# THAT4305_Comp_CE.net
KiCad netlist of a schematic drawn in EAGLE
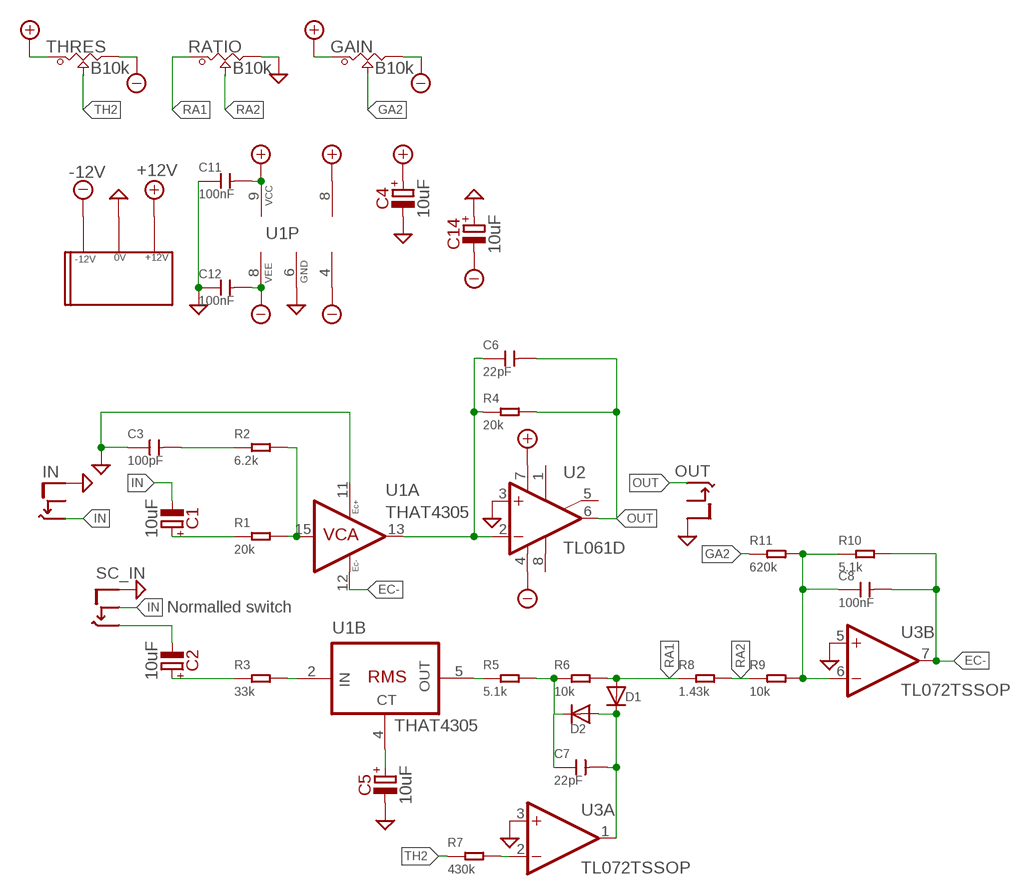
[diagram p0: schematic, sheet 1]

(export (version "E")
  (design (tool "Eeschema 10.0.6"))
  (components
    (comp (ref "C1")
      (value "10uF")
      (footprint "eagle-import:PAN_B")
      (libsource (lib "eagle-import") (part "PAN_B"))
    )
    (comp (ref "C2")
      (value "10uF")
      (footprint "eagle-import:PAN_B")
      (libsource (lib "eagle-import") (part "PAN_B"))
    )
    (comp (ref "C3")
      (value "100pF")
      (footprint "eagle-import:C0805")
      (fields (field (name "MPN") "CC0805KKX7R8BB105"))
      (libsource (lib "eagle-import") (part "CERAMIC-1UF-25V-10%-X7R(0805)"))
    )
    (comp (ref "C4")
      (value "10uF")
      (footprint "eagle-import:PAN_B")
      (libsource (lib "eagle-import") (part "PAN_B"))
    )
    (comp (ref "C5")
      (value "10uF")
      (footprint "eagle-import:PAN_B")
      (libsource (lib "eagle-import") (part "PAN_B"))
    )
    (comp (ref "C6")
      (value "22pF")
      (footprint "eagle-import:C0805")
      (fields (field (name "MPN") "CC0805KKX7R8BB105"))
      (libsource (lib "eagle-import") (part "CERAMIC-1UF-25V-10%-X7R(0805)"))
    )
    (comp (ref "C7")
      (value "22pF")
      (footprint "eagle-import:C0805")
      (fields (field (name "MPN") "CC0805KKX7R8BB105"))
      (libsource (lib "eagle-import") (part "CERAMIC-1UF-25V-10%-X7R(0805)"))
    )
    (comp (ref "C8")
      (value "100nF")
      (footprint "eagle-import:C0805")
      (fields (field (name "MPN") "CC0805KKX7R8BB105"))
      (libsource (lib "eagle-import") (part "CERAMIC-1UF-25V-10%-X7R(0805)"))
    )
    (comp (ref "C11")
      (value "100nF")
      (footprint "eagle-import:C0805")
      (fields (field (name "MPN") "CC0805KKX7R8BB105"))
      (libsource (lib "eagle-import") (part "CERAMIC-1UF-25V-10%-X7R(0805)"))
    )
    (comp (ref "C12")
      (value "100nF")
      (footprint "eagle-import:C0805")
      (fields (field (name "MPN") "CC0805KKX7R8BB105"))
      (libsource (lib "eagle-import") (part "CERAMIC-1UF-25V-10%-X7R(0805)"))
    )
    (comp (ref "C14")
      (value "10uF")
      (footprint "eagle-import:PAN_B")
      (libsource (lib "eagle-import") (part "PAN_B"))
    )
    (comp (ref "D1")
      (value "DIODESOD-123")
      (footprint "eagle-import:SOD-123")
      (libsource (lib "eagle-import") (part "DIODESOD-123"))
    )
    (comp (ref "D2")
      (value "DIODESOD-123")
      (footprint "eagle-import:SOD-123")
      (libsource (lib "eagle-import") (part "DIODESOD-123"))
    )
    (comp (ref "GAIN")
      (value "B10k")
      (footprint "eagle-import:POT_9MM_SMD")
      (libsource (lib "eagle-import") (part "POT_9MM_SMD"))
    )
    (comp (ref "R1")
      (value "20k")
      (footprint "eagle-import:R0805")
      (fields (field (name "MPN") "RC0805JR-071KL"))
      (libsource (lib "eagle-import") (part "SMD-RES-20K-5%-1/8W(0805)"))
    )
    (comp (ref "R2")
      (value "6.2k")
      (footprint "eagle-import:R0805")
      (fields (field (name "MPN") "RC0805JR-071KL"))
      (libsource (lib "eagle-import") (part "SMD-RES-20K-5%-1/8W(0805)"))
    )
    (comp (ref "R3")
      (value "33k")
      (footprint "eagle-import:R0805")
      (fields (field (name "MPN") "RC0805JR-071KL"))
      (libsource (lib "eagle-import") (part "SMD-RES-20K-5%-1/8W(0805)"))
    )
    (comp (ref "R4")
      (value "20k")
      (footprint "eagle-import:R0805")
      (fields (field (name "MPN") "RC0805JR-071KL"))
      (libsource (lib "eagle-import") (part "SMD-RES-20K-5%-1/8W(0805)"))
    )
    (comp (ref "R5")
      (value "5.1k")
      (footprint "eagle-import:R0805")
      (fields (field (name "MPN") "RC0805JR-071KL"))
      (libsource (lib "eagle-import") (part "SMD-RES-20K-5%-1/8W(0805)"))
    )
    (comp (ref "R6")
      (value "10k")
      (footprint "eagle-import:R0805")
      (fields (field (name "MPN") "RC0805JR-071KL"))
      (libsource (lib "eagle-import") (part "SMD-RES-20K-5%-1/8W(0805)"))
    )
    (comp (ref "R7")
      (value "430k")
      (footprint "eagle-import:R0805")
      (fields (field (name "MPN") "RC0805JR-071KL"))
      (libsource (lib "eagle-import") (part "SMD-RES-20K-5%-1/8W(0805)"))
    )
    (comp (ref "R8")
      (value "1.43k")
      (footprint "eagle-import:R0805")
      (fields (field (name "MPN") "RC0805JR-071KL"))
      (libsource (lib "eagle-import") (part "SMD-RES-20K-5%-1/8W(0805)"))
    )
    (comp (ref "R9")
      (value "10k")
      (footprint "eagle-import:R0805")
      (fields (field (name "MPN") "RC0805JR-071KL"))
      (libsource (lib "eagle-import") (part "SMD-RES-20K-5%-1/8W(0805)"))
    )
    (comp (ref "R10")
      (value "5.1k")
      (footprint "eagle-import:R0805")
      (fields (field (name "MPN") "RC0805JR-071KL"))
      (libsource (lib "eagle-import") (part "SMD-RES-20K-5%-1/8W(0805)"))
    )
    (comp (ref "R11")
      (value "620k")
      (footprint "eagle-import:R0805")
      (fields (field (name "MPN") "RC0805JR-071KL"))
      (libsource (lib "eagle-import") (part "SMD-RES-20K-5%-1/8W(0805)"))
    )
    (comp (ref "RATIO")
      (value "B10k")
      (footprint "eagle-import:POT_9MM_SMD")
      (libsource (lib "eagle-import") (part "POT_9MM_SMD"))
    )
    (comp (ref "THRES")
      (value "B10k")
      (footprint "eagle-import:POT_9MM_SMD")
      (libsource (lib "eagle-import") (part "POT_9MM_SMD"))
    )
    (comp (ref "U$2")
      (value "EURO_POW_CEH")
      (footprint "eagle-import:EURO_POW_CEH")
      (libsource (lib "eagle-import") (part "EURO_POW_CEH"))
    )
    (comp (ref "U$3")
      (value "THONKICONN_CE_3X_COMG_1SW")
      (footprint "eagle-import:1.27MM_CE_4X_COMG_NOSW")
      (libsource (lib "eagle-import") (part "THONKICONN_CE_3X_COMG_1SW"))
    )
    (comp (ref "U1")
      (value "THAT4305")
      (footprint "eagle-import:QSOP16")
      (libsource (lib "eagle-import") (part "THAT4305Q16-U"))
    )
    (comp (ref "U2")
      (value "TL061D")
      (footprint "eagle-import:SO08")
      (libsource (lib "eagle-import") (part "TL061D"))
    )
    (comp (ref "U3")
      (value "TL072TSSOP")
      (footprint "eagle-import:TSSOP-8")
      (libsource (lib "eagle-import") (part "TL072TSSOP"))
    )
  )
  (nets
    (net (code "1") (name "+12V") (class "Default")
      (node (ref "C11") (pin "2") (pinfunction "2_2") (pintype "passive"))
      (node (ref "C4") (pin "1+") (pinfunction "+_1+") (pintype "passive"))
      (node (ref "GAIN") (pin "1") (pinfunction "1_1") (pintype "bidirectional"))
      (node (ref "THRES") (pin "1") (pinfunction "1_1") (pintype "bidirectional"))
      (node (ref "U$2") (pin "+12V") (pinfunction "+12V_+12V") (pintype "bidirectional"))
      (node (ref "U1") (pin "9") (pinfunction "VCC_9") (pintype "power_in"))
      (node (ref "U2") (pin "7") (pinfunction "V+_7") (pintype "power_in"))
      (node (ref "U3") (pin "8") (pinfunction "V+_8") (pintype "power_in"))
    )
    (net (code "2") (name "-12V") (class "Default")
      (node (ref "C12") (pin "2") (pinfunction "2_2") (pintype "passive"))
      (node (ref "C14") (pin "2-") (pinfunction "-_2-") (pintype "passive"))
      (node (ref "GAIN") (pin "3") (pinfunction "3_3") (pintype "bidirectional"))
      (node (ref "THRES") (pin "3") (pinfunction "3_3") (pintype "bidirectional"))
      (node (ref "U$2") (pin "-12V") (pinfunction "-12V_-12V") (pintype "bidirectional"))
      (node (ref "U1") (pin "8") (pinfunction "VEE_8") (pintype "power_in"))
      (node (ref "U2") (pin "4") (pinfunction "V-_4") (pintype "power_in"))
      (node (ref "U3") (pin "4") (pinfunction "V-_4") (pintype "power_in"))
    )
    (net (code "3") (name "EC-") (class "Default")
      (node (ref "C8") (pin "2") (pinfunction "2_2") (pintype "passive"))
      (node (ref "R10") (pin "2") (pinfunction "2_2") (pintype "passive"))
      (node (ref "U1") (pin "12") (pinfunction "EC-_12") (pintype "passive"))
      (node (ref "U3") (pin "7") (pinfunction "OUT_7") (pintype "output"))
    )
    (net (code "4") (name "GA2") (class "Default")
      (node (ref "GAIN") (pin "2") (pinfunction "2_2") (pintype "bidirectional"))
      (node (ref "R11") (pin "1") (pinfunction "1_1") (pintype "passive"))
    )
    (net (code "5") (name "GND") (class "Default")
      (node (ref "C11") (pin "1") (pinfunction "1_1") (pintype "passive"))
      (node (ref "C12") (pin "1") (pinfunction "1_1") (pintype "passive"))
      (node (ref "C14") (pin "1+") (pinfunction "+_1+") (pintype "passive"))
      (node (ref "C3") (pin "1") (pinfunction "1_1") (pintype "passive"))
      (node (ref "C4") (pin "2-") (pinfunction "-_2-") (pintype "passive"))
      (node (ref "C5") (pin "2-") (pinfunction "-_2-") (pintype "passive"))
      (node (ref "RATIO") (pin "3") (pinfunction "3_3") (pintype "bidirectional"))
      (node (ref "U$2") (pin "GND") (pinfunction "GND_GND") (pintype "bidirectional"))
      (node (ref "U$3") (pin "0") (pinfunction "S_0") (pintype "bidirectional"))
      (node (ref "U1") (pin "11") (pinfunction "EC+_11") (pintype "passive"))
      (node (ref "U1") (pin "6") (pinfunction "GND_6") (pintype "power_in"))
      (node (ref "U2") (pin "3") (pinfunction "+IN_3") (pintype "input"))
      (node (ref "U3") (pin "3") (pinfunction "+IN_3") (pintype "input"))
      (node (ref "U3") (pin "5") (pinfunction "+IN_5") (pintype "input"))
    )
    (net (code "6") (name "IN") (class "Default")
      (node (ref "C1") (pin "2-") (pinfunction "-_2-") (pintype "passive"))
      (node (ref "U$3") (pin "2") (pinfunction "SW_2") (pintype "bidirectional"))
      (node (ref "U$3") (pin "3") (pinfunction "T_3") (pintype "bidirectional"))
    )
    (net (code "7") (name "Net-(C1-+)") (class "Default")
      (node (ref "C1") (pin "1+") (pinfunction "+_1+") (pintype "passive"))
      (node (ref "R1") (pin "1") (pinfunction "1_1") (pintype "passive"))
    )
    (net (code "8") (name "Net-(C2-+)") (class "Default")
      (node (ref "C2") (pin "1+") (pinfunction "+_1+") (pintype "passive"))
      (node (ref "R3") (pin "1") (pinfunction "1_1") (pintype "passive"))
    )
    (net (code "9") (name "Net-(C2--)") (class "Default")
      (node (ref "C2") (pin "2-") (pinfunction "-_2-") (pintype "passive"))
      (node (ref "U$3") (pin "1") (pinfunction "T_1") (pintype "bidirectional"))
    )
    (net (code "10") (name "Net-(C3-Pad2)") (class "Default")
      (node (ref "C3") (pin "2") (pinfunction "2_2") (pintype "passive"))
      (node (ref "R2") (pin "1") (pinfunction "1_1") (pintype "passive"))
    )
    (net (code "11") (name "Net-(C5-+)") (class "Default")
      (node (ref "C5") (pin "1+") (pinfunction "+_1+") (pintype "passive"))
      (node (ref "U1") (pin "4") (pinfunction "CT_4") (pintype "passive"))
    )
    (net (code "12") (name "Net-(C7-Pad1)") (class "Default")
      (node (ref "C7") (pin "1") (pinfunction "1_1") (pintype "passive"))
      (node (ref "D2") (pin "C") (pinfunction "C_C") (pintype "passive"))
      (node (ref "R5") (pin "2") (pinfunction "2_2") (pintype "passive"))
      (node (ref "R6") (pin "1") (pinfunction "1_1") (pintype "passive"))
    )
    (net (code "13") (name "Net-(U1A-VCA_IN)") (class "Default")
      (node (ref "R1") (pin "2") (pinfunction "2_2") (pintype "passive"))
      (node (ref "R2") (pin "2") (pinfunction "2_2") (pintype "passive"))
      (node (ref "U1") (pin "15") (pinfunction "VCA_IN_15") (pintype "input"))
    )
    (net (code "14") (name "Net-(U1A-VCA_OUT)") (class "Default")
      (node (ref "C6") (pin "1") (pinfunction "1_1") (pintype "passive"))
      (node (ref "R4") (pin "1") (pinfunction "1_1") (pintype "passive"))
      (node (ref "U1") (pin "13") (pinfunction "VCA_OUT_13") (pintype "output"))
      (node (ref "U2") (pin "2") (pinfunction "-IN_2") (pintype "input"))
    )
    (net (code "15") (name "Net-(U1B-RMS_IN)") (class "Default")
      (node (ref "R3") (pin "2") (pinfunction "2_2") (pintype "passive"))
      (node (ref "U1") (pin "2") (pinfunction "RMS_IN_2") (pintype "input"))
    )
    (net (code "16") (name "Net-(U1B-RMS_OUT)") (class "Default")
      (node (ref "R5") (pin "1") (pinfunction "1_1") (pintype "passive"))
      (node (ref "U1") (pin "5") (pinfunction "RMS_OUT_5") (pintype "output"))
    )
    (net (code "17") (name "Net-(U3A--IN)") (class "Default")
      (node (ref "R7") (pin "2") (pinfunction "2_2") (pintype "passive"))
      (node (ref "U3") (pin "2") (pinfunction "-IN_2") (pintype "input"))
    )
    (net (code "18") (name "Net-(U3A-OUT)") (class "Default")
      (node (ref "C7") (pin "2") (pinfunction "2_2") (pintype "passive"))
      (node (ref "D1") (pin "C") (pinfunction "C_C") (pintype "passive"))
      (node (ref "D2") (pin "A") (pinfunction "A_A") (pintype "passive"))
      (node (ref "U3") (pin "1") (pinfunction "OUT_1") (pintype "output"))
    )
    (net (code "19") (name "Net-(U3B--IN)") (class "Default")
      (node (ref "C8") (pin "1") (pinfunction "1_1") (pintype "passive"))
      (node (ref "R10") (pin "1") (pinfunction "1_1") (pintype "passive"))
      (node (ref "R11") (pin "2") (pinfunction "2_2") (pintype "passive"))
      (node (ref "R9") (pin "2") (pinfunction "2_2") (pintype "passive"))
      (node (ref "U3") (pin "6") (pinfunction "-IN_6") (pintype "input"))
    )
    (net (code "20") (name "OUT") (class "Default")
      (node (ref "C6") (pin "2") (pinfunction "2_2") (pintype "passive"))
      (node (ref "R4") (pin "2") (pinfunction "2_2") (pintype "passive"))
      (node (ref "U$3") (pin "4") (pinfunction "T_4") (pintype "bidirectional"))
      (node (ref "U2") (pin "6") (pinfunction "OUT_6") (pintype "output"))
    )
    (net (code "21") (name "RA1") (class "Default")
      (node (ref "D1") (pin "A") (pinfunction "A_A") (pintype "passive"))
      (node (ref "R6") (pin "2") (pinfunction "2_2") (pintype "passive"))
      (node (ref "R8") (pin "1") (pinfunction "1_1") (pintype "passive"))
      (node (ref "RATIO") (pin "1") (pinfunction "1_1") (pintype "bidirectional"))
    )
    (net (code "22") (name "RA2") (class "Default")
      (node (ref "R8") (pin "2") (pinfunction "2_2") (pintype "passive"))
      (node (ref "R9") (pin "1") (pinfunction "1_1") (pintype "passive"))
      (node (ref "RATIO") (pin "2") (pinfunction "2_2") (pintype "bidirectional"))
    )
    (net (code "23") (name "TH2") (class "Default")
      (node (ref "R7") (pin "1") (pinfunction "1_1") (pintype "passive"))
      (node (ref "THRES") (pin "2") (pinfunction "2_2") (pintype "bidirectional"))
    )
    (net (code "24") (name "unconnected-(U2-ON1-Pad1)") (class "Default")
      (node (ref "U2") (pin "1") (pinfunction "ON1_1") (pintype "passive"))
    )
    (net (code "25") (name "unconnected-(U2-ON2-Pad5)") (class "Default")
      (node (ref "U2") (pin "5") (pinfunction "ON2_5") (pintype "passive"))
    )
    (net (code "26") (name "unconnected-(U2-OPT-Pad8)") (class "Default")
      (node (ref "U2") (pin "8") (pinfunction "OPT_8") (pintype "passive"))
    )
  )
)
